# I2CTemprature.net
KiCad netlist of a schematic drawn in Altium Designer
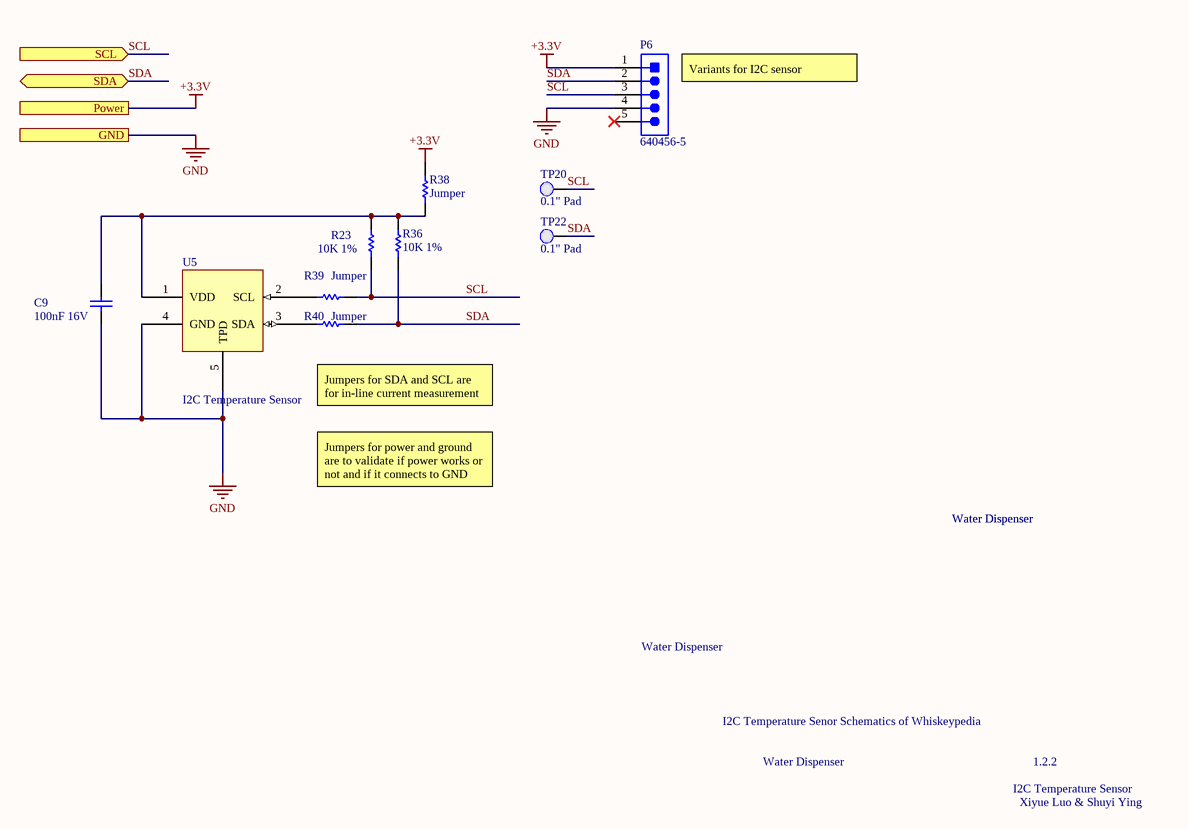
[diagram p0: I2CTemprature.SchDoc]

(export (version "E")
  (design (tool "Eeschema 10.0.6"))
  (components
    (comp (ref "C9")
      (value "100nF 16V")
      (footprint "CAPC0603(1608)100_N")
      (description "CAP 100nF 16V ±10% 0603 (1608 Metric) Thickness 1mm SMD")
      (fields (field (name "TOLERANCE") "Â±10%"))
      (libsource (lib "Altium Content Vault") (part "CAP"))
    )
    (comp (ref "P6")
      (value "640456-5")
      (footprint "TECO-640456-5")
      (fields (field (name "MANUFACTURER") "TE Connectivity"))
      (libsource (lib "Altium Content Vault") (part "CN-1P-M-R5"))
    )
    (comp (ref "R23")
      (value "10K 1%")
      (footprint "RESC0603(1608)_N")
      (description "10K 0.1W 1% 0603 (1608 Metric)  SMD")
      (fields (field (name "POWER") "0.1 W") (field (name "TOLERANCE") "1 %"))
      (libsource (lib "Altium Content Vault") (part "RES"))
    )
    (comp (ref "R36")
      (value "10K 1%")
      (footprint "RESC0603(1608)_N")
      (description "10K 0.1W 1% 0603 (1608 Metric)  SMD")
      (fields (field (name "POWER") "0.1 W") (field (name "TOLERANCE") "1 %"))
      (libsource (lib "Altium Content Vault") (part "RES"))
    )
    (comp (ref "R38")
      (value "Jumper")
      (footprint "RESC0805(2012)_N")
      (description "Jumper 0805 (2012 Metric)")
      (fields (field (name "TOLERANCE") "None"))
      (libsource (lib "Altium Content Vault") (part "RES"))
    )
    (comp (ref "R39")
      (value "Jumper")
      (footprint "RESC0805(2012)_N")
      (description "Jumper 0805 (2012 Metric)")
      (fields (field (name "TOLERANCE") "None"))
      (libsource (lib "Altium Content Vault") (part "RES"))
    )
    (comp (ref "R40")
      (value "Jumper")
      (footprint "RESC0805(2012)_N")
      (description "Jumper 0805 (2012 Metric)")
      (fields (field (name "TOLERANCE") "None"))
      (libsource (lib "Altium Content Vault") (part "RES"))
    )
    (comp (ref "TP20")
      (value "0.1\" Pad")
      (footprint "PCBComponent")
      (libsource (lib "Components - 12.02.20 - 18.05") (part "0.1{dblquote} Pad-A.4"))
    )
    (comp (ref "TP22")
      (value "0.1\" Pad")
      (footprint "PCBComponent")
      (libsource (lib "Components - 12.02.20 - 18.05") (part "0.1{dblquote} Pad-A.4"))
    )
    (comp (ref "U5")
      (value "I2C Temperature Sensor")
      (footprint "SHTC3")
      (description "Relative Humidity & Temperature Sensor, consumer focus")
      (fields
        (field (name "MANUFACTURER") "Sensirion")
        (field (name "MANUFACTURER PART NUMBER") "SHTC3-TR-2.5KS")
      )
      (libsource (lib "Whiskeypedia_Components") (part "SHTC3-TR-2.5KS"))
    )
  )
  (nets
    (net (code "1") (name "+3.3V") (class "Default")
      (node (ref "P6") (pin "1") (pinfunction "DTR_1") (pintype "passive"))
      (node (ref "R38") (pin "2") (pinfunction "2_2") (pintype "passive"))
    )
    (net (code "2") (name "/SCL") (class "Default")
      (node (ref "P6") (pin "3") (pinfunction "TXO_3") (pintype "passive"))
      (node (ref "R23") (pin "1") (pinfunction "1_1") (pintype "passive"))
      (node (ref "R39") (pin "2") (pinfunction "2_2") (pintype "passive"))
      (node (ref "TP20") (pin "1") (pinfunction "PAD_1") (pintype "passive"))
    )
    (net (code "3") (name "/SDA") (class "Default")
      (node (ref "P6") (pin "2") (pinfunction "RXI_2") (pintype "passive"))
      (node (ref "R36") (pin "1") (pinfunction "1_1") (pintype "passive"))
      (node (ref "R40") (pin "2") (pinfunction "2_2") (pintype "passive"))
      (node (ref "TP22") (pin "1") (pinfunction "PAD_1") (pintype "passive"))
    )
    (net (code "4") (name "GND") (class "Default")
      (node (ref "C9") (pin "1") (pinfunction "1_1") (pintype "passive"))
      (node (ref "P6") (pin "4") (pinfunction "VCC_4") (pintype "passive"))
      (node (ref "U5") (pin "4") (pinfunction "GND_4") (pintype "power_in"))
      (node (ref "U5") (pin "5") (pinfunction "TPD_5") (pintype "passive"))
    )
    (net (code "5") (name "Net-(U5-SCL)") (class "Default")
      (node (ref "R39") (pin "1") (pinfunction "1_1") (pintype "passive"))
      (node (ref "U5") (pin "2") (pinfunction "SCL_2") (pintype "input"))
    )
    (net (code "6") (name "Net-(U5-SDA)") (class "Default")
      (node (ref "R40") (pin "1") (pinfunction "1_1") (pintype "passive"))
      (node (ref "U5") (pin "3") (pinfunction "SDA_3") (pintype "bidirectional"))
    )
    (net (code "7") (name "Net-(U5-VDD)") (class "Default")
      (node (ref "C9") (pin "2") (pinfunction "2_2") (pintype "passive"))
      (node (ref "R23") (pin "2") (pinfunction "2_2") (pintype "passive"))
      (node (ref "R36") (pin "2") (pinfunction "2_2") (pintype "passive"))
      (node (ref "R38") (pin "1") (pinfunction "1_1") (pintype "passive"))
      (node (ref "U5") (pin "1") (pinfunction "VDD_1") (pintype "power_in"))
    )
    (net (code "8") (name "unconnected-(P6-CTS-Pad5)") (class "Default")
      (node (ref "P6") (pin "5") (pinfunction "CTS_5") (pintype "passive+no_connect"))
    )
  )
)
